# PTC_Control_V2.net
KiCad netlist of a schematic drawn in EAGLE
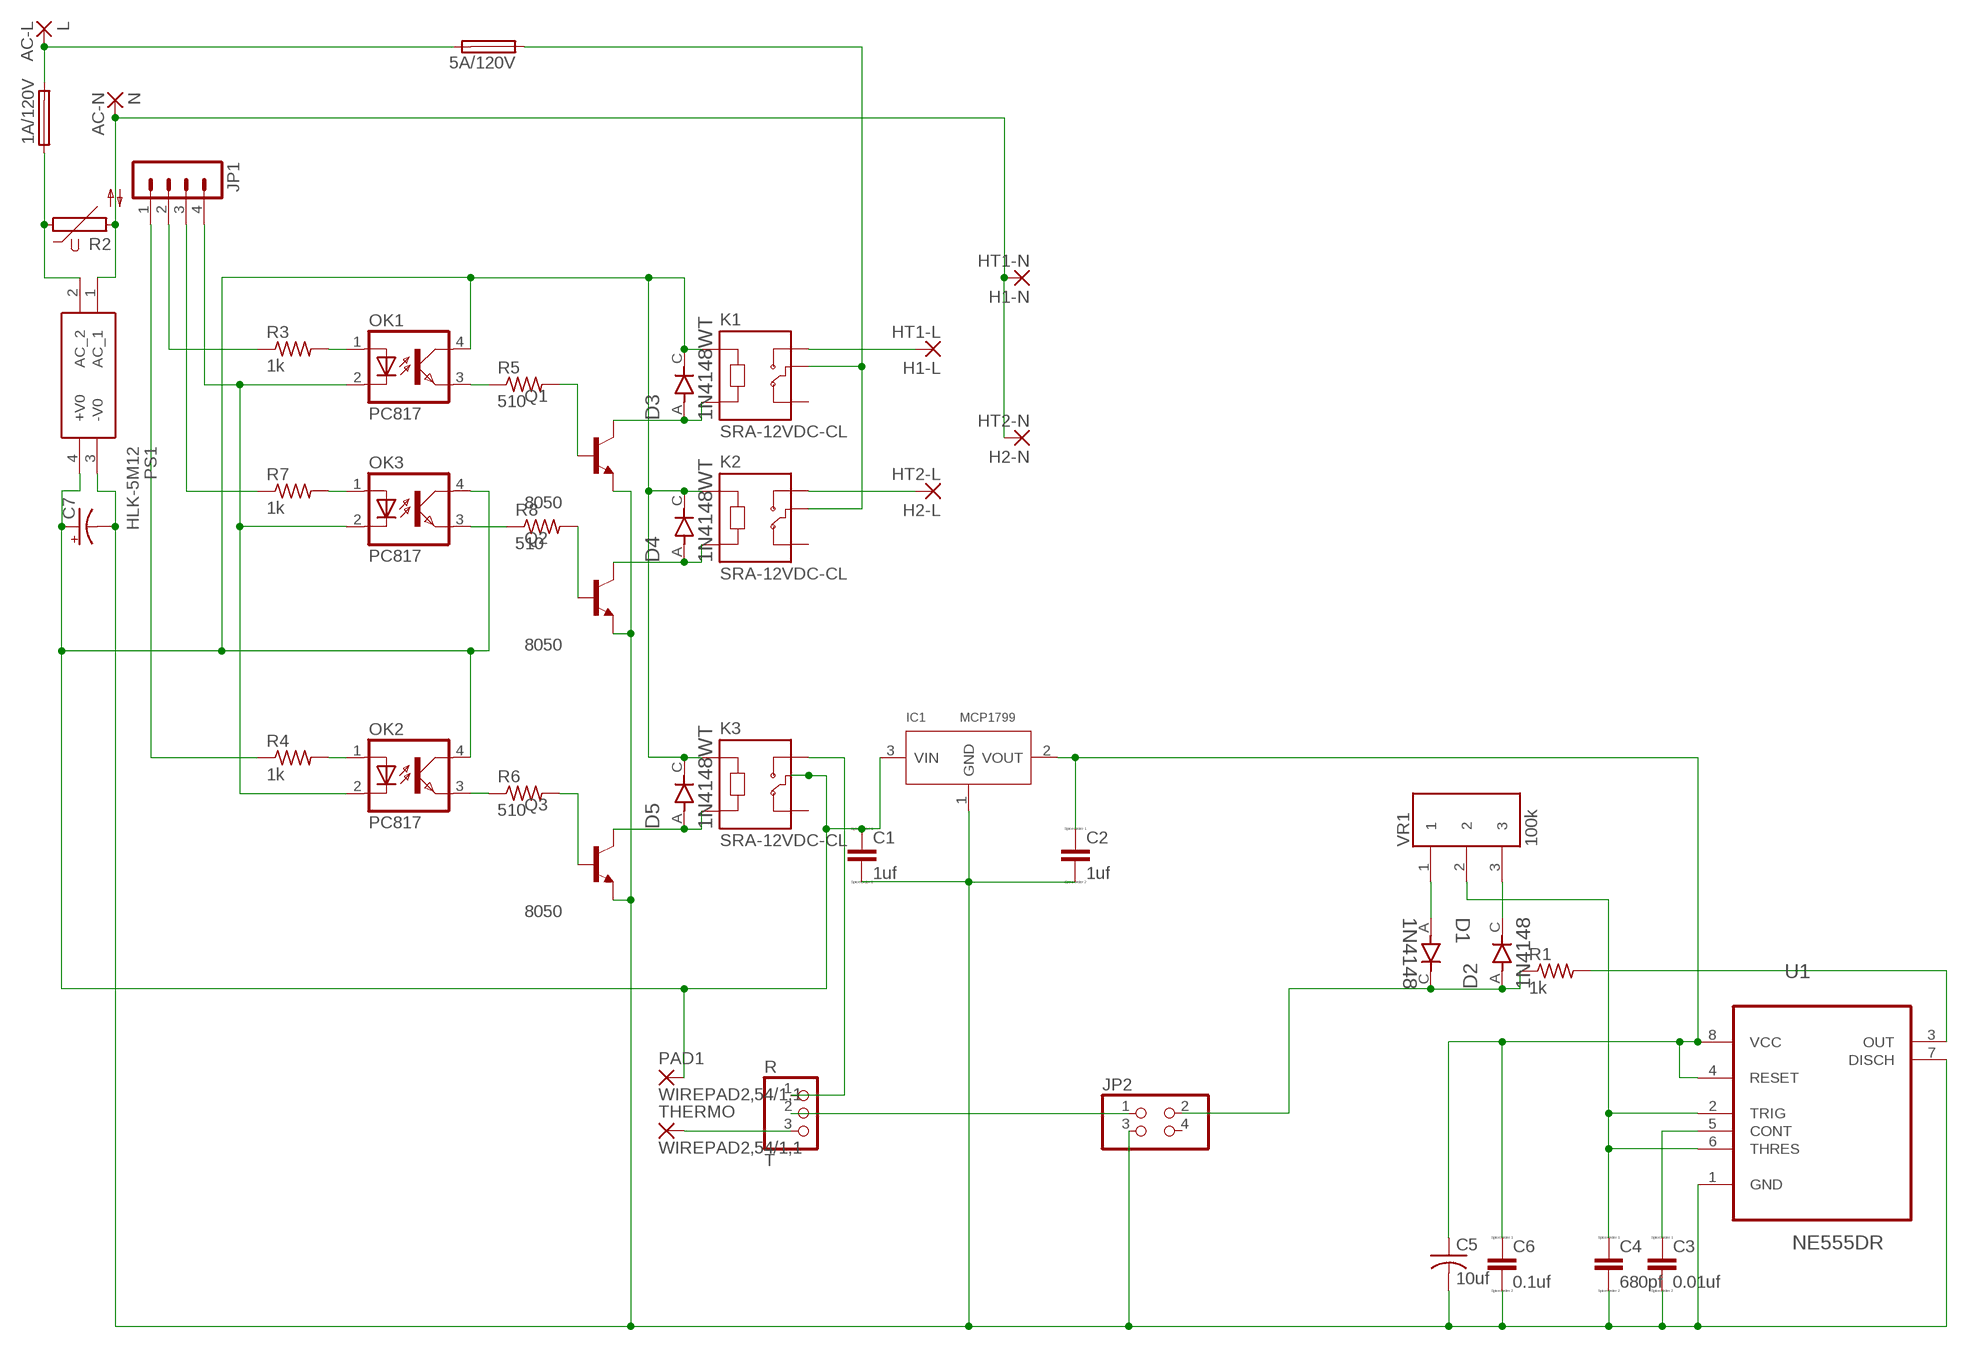
[diagram p0: schematic, sheet 1]

(export (version "E")
  (design (tool "Eeschema 10.0.6"))
  (components
    (comp (ref "1A/120V")
      (value "SH25")
      (footprint "eagle-import:SH25")
      (fields (field (name "MF") "SCHURTER") (field (name "MPN") "0031.8211"))
      (libsource (lib "eagle-import") (part "SH25"))
    )
    (comp (ref "5A/120V")
      (value "SH25")
      (footprint "eagle-import:SH25")
      (fields (field (name "MF") "SCHURTER") (field (name "MPN") "0031.8211"))
      (libsource (lib "eagle-import") (part "SH25"))
    )
    (comp (ref "C1")
      (value "1uf")
      (footprint "eagle-import:C0805")
      (libsource (lib "eagle-import") (part "C"))
    )
    (comp (ref "C2")
      (value "1uf")
      (footprint "eagle-import:C0805")
      (libsource (lib "eagle-import") (part "C"))
    )
    (comp (ref "C3")
      (value "0.01uf")
      (footprint "eagle-import:C0805")
      (libsource (lib "eagle-import") (part "C"))
    )
    (comp (ref "C4")
      (value "680pf")
      (footprint "eagle-import:C0805")
      (libsource (lib "eagle-import") (part "C"))
    )
    (comp (ref "C5")
      (value "10uf")
      (footprint "eagle-import:C1206")
      (libsource (lib "eagle-import") (part "C-USC1206"))
    )
    (comp (ref "C6")
      (value "0.1uf")
      (footprint "eagle-import:C0805")
      (libsource (lib "eagle-import") (part "C"))
    )
    (comp (ref "C7")
      (value "CPOL-USE3.5-8")
      (footprint "eagle-import:E3,5-8")
      (libsource (lib "eagle-import") (part "CPOL-USE3.5-8"))
    )
    (comp (ref "D1")
      (value "1N4148")
      (footprint "eagle-import:SODFL1608X70N")
      (fields (field (name "MF") "ON Semiconductor") (field (name "MP") "1N4148WT"))
      (libsource (lib "eagle-import") (part "1N4148WT"))
    )
    (comp (ref "D2")
      (value "1N4148")
      (footprint "eagle-import:SODFL1608X70N")
      (fields (field (name "MF") "ON Semiconductor") (field (name "MP") "1N4148WT"))
      (libsource (lib "eagle-import") (part "1N4148WT"))
    )
    (comp (ref "D3")
      (value "1N4148WT")
      (footprint "eagle-import:SODFL1608X70N")
      (fields (field (name "MF") "ON Semiconductor"))
      (libsource (lib "eagle-import") (part "1N4148WT"))
    )
    (comp (ref "D4")
      (value "1N4148WT")
      (footprint "eagle-import:SODFL1608X70N")
      (fields (field (name "MF") "ON Semiconductor"))
      (libsource (lib "eagle-import") (part "1N4148WT"))
    )
    (comp (ref "D5")
      (value "1N4148WT")
      (footprint "eagle-import:SODFL1608X70N")
      (fields (field (name "MF") "ON Semiconductor"))
      (libsource (lib "eagle-import") (part "1N4148WT"))
    )
    (comp (ref "H1-L")
      (value "HT1-L")
      (footprint "eagle-import:3,17_1,2")
      (libsource (lib "eagle-import") (part "WIREPAD3,17/1,2"))
    )
    (comp (ref "H1-N")
      (value "HT1-N")
      (footprint "eagle-import:3,17_1,2")
      (libsource (lib "eagle-import") (part "WIREPAD3,17/1,2"))
    )
    (comp (ref "H2-L")
      (value "HT2-L")
      (footprint "eagle-import:3,17_1,2")
      (libsource (lib "eagle-import") (part "WIREPAD3,17/1,2"))
    )
    (comp (ref "H2-N")
      (value "HT2-N")
      (footprint "eagle-import:3,17_1,2")
      (libsource (lib "eagle-import") (part "WIREPAD3,17/1,2"))
    )
    (comp (ref "IC1")
      (value "MCP1799")
      (footprint "eagle-import:SOT-23")
      (fields (field (name "MF") "Torex") (field (name "MP") "XC6206P252MR-G"))
      (libsource (lib "eagle-import") (part "PMIC-LDO-XC6206P252MR-G(SOT23)"))
    )
    (comp (ref "JP1")
      (value "MA04-1")
      (footprint "eagle-import:MA04-1")
      (libsource (lib "eagle-import") (part "MA04-1"))
    )
    (comp (ref "JP2")
      (value "PINHD-2X2")
      (footprint "eagle-import:2X02")
      (libsource (lib "eagle-import") (part "PINHD-2X2"))
    )
    (comp (ref "K1")
      (value "SRA-12VDC-CL")
      (footprint "eagle-import:RELAY_1-1721150-3")
      (fields
        (field (name "COMMENT") "1-1721150-3")
        (field (name "MF") "TE Connectivity")
        (field (name "MP") "ORWH-SH-112D1F,000")
      )
      (libsource (lib "eagle-import") (part "1-1721150-3"))
    )
    (comp (ref "K2")
      (value "SRA-12VDC-CL")
      (footprint "eagle-import:RELAY_1-1721150-3")
      (fields
        (field (name "COMMENT") "1-1721150-3")
        (field (name "MF") "TE Connectivity")
        (field (name "MP") "ORWH-SH-112D1F,000")
      )
      (libsource (lib "eagle-import") (part "1-1721150-3"))
    )
    (comp (ref "K3")
      (value "SRA-12VDC-CL")
      (footprint "eagle-import:RELAY_1-1721150-3")
      (fields
        (field (name "COMMENT") "1-1721150-3")
        (field (name "MF") "TE Connectivity")
        (field (name "MP") "ORWH-SH-112D1F,000")
      )
      (libsource (lib "eagle-import") (part "1-1721150-3"))
    )
    (comp (ref "L")
      (value "AC-L")
      (footprint "eagle-import:3,81_1,4")
      (libsource (lib "eagle-import") (part "WIREPAD3,81/1,4"))
    )
    (comp (ref "N")
      (value "AC-N")
      (footprint "eagle-import:3,81_1,4")
      (libsource (lib "eagle-import") (part "WIREPAD3,81/1,4"))
    )
    (comp (ref "OK1")
      (value "PC817")
      (footprint "eagle-import:DIL04")
      (fields (field (name "MPN") "PC817X4J000F"))
      (libsource (lib "eagle-import") (part "PC817"))
    )
    (comp (ref "OK2")
      (value "PC817")
      (footprint "eagle-import:DIL04")
      (fields (field (name "MPN") "PC817X4J000F"))
      (libsource (lib "eagle-import") (part "PC817"))
    )
    (comp (ref "OK3")
      (value "PC817")
      (footprint "eagle-import:DIL04")
      (fields (field (name "MPN") "PC817X4J000F"))
      (libsource (lib "eagle-import") (part "PC817"))
    )
    (comp (ref "PAD1")
      (value "WIREPAD2,54/1,1")
      (footprint "eagle-import:2,54_1,1")
      (libsource (lib "eagle-import") (part "WIREPAD2,54/1,1"))
    )
    (comp (ref "PS1")
      (value "HLK-5M12")
      (footprint "eagle-import:HLK5M12")
      (libsource (lib "eagle-import") (part "HLK-5M12"))
    )
    (comp (ref "Q1")
      (value "8050")
      (footprint "eagle-import:TRANS_MMSS8050-H-TP")
      (fields (field (name "MF") "Micro Commercial") (field (name "MP") "MMSS8050-H-TP"))
      (libsource (lib "eagle-import") (part "MMSS8050-H-TP"))
    )
    (comp (ref "Q2")
      (value "8050")
      (footprint "eagle-import:TRANS_MMSS8050-H-TP")
      (fields (field (name "MF") "Micro Commercial") (field (name "MP") "MMSS8050-H-TP"))
      (libsource (lib "eagle-import") (part "MMSS8050-H-TP"))
    )
    (comp (ref "Q3")
      (value "8050")
      (footprint "eagle-import:TRANS_MMSS8050-H-TP")
      (fields (field (name "MF") "Micro Commercial") (field (name "MP") "MMSS8050-H-TP"))
      (libsource (lib "eagle-import") (part "MMSS8050-H-TP"))
    )
    (comp (ref "R")
      (value "T")
      (footprint "eagle-import:1X03")
      (libsource (lib "eagle-import") (part "PINHD-1X3"))
    )
    (comp (ref "R1")
      (value "1k")
      (footprint "eagle-import:R0805")
      (libsource (lib "eagle-import") (part "R-US_R0805"))
    )
    (comp (ref "R2")
      (value "S10K250")
      (footprint "eagle-import:S10K250")
      (libsource (lib "eagle-import") (part "S10K250"))
    )
    (comp (ref "R3")
      (value "1k")
      (footprint "eagle-import:R0805")
      (libsource (lib "eagle-import") (part "R-US_R0805"))
    )
    (comp (ref "R4")
      (value "1k")
      (footprint "eagle-import:R0805")
      (libsource (lib "eagle-import") (part "R-US_R0805"))
    )
    (comp (ref "R5")
      (value "510")
      (footprint "eagle-import:R0805")
      (libsource (lib "eagle-import") (part "R-US_R0805"))
    )
    (comp (ref "R6")
      (value "510")
      (footprint "eagle-import:R0805")
      (libsource (lib "eagle-import") (part "R-US_R0805"))
    )
    (comp (ref "R7")
      (value "1k")
      (footprint "eagle-import:R0805")
      (libsource (lib "eagle-import") (part "R-US_R0805"))
    )
    (comp (ref "R8")
      (value "510")
      (footprint "eagle-import:R0805")
      (libsource (lib "eagle-import") (part "R-US_R0805"))
    )
    (comp (ref "THERMO")
      (value "WIREPAD2,54/1,1")
      (footprint "eagle-import:2,54_1,1")
      (libsource (lib "eagle-import") (part "WIREPAD2,54/1,1"))
    )
    (comp (ref "U1")
      (value "NE555DR")
      (footprint "eagle-import:SOIC127P600X175-8N")
      (libsource (lib "eagle-import") (part "NE555DR"))
    )
    (comp (ref "VR1")
      (value "100k")
      (footprint "eagle-import:TRIM_416XA503P")
      (fields
        (field (name "COMMENT") "1623895-9")
        (field (name "MF") "TE Connectivity")
        (field (name "MP") "416XA503P")
      )
      (libsource (lib "eagle-import") (part "416XA503P"))
    )
  )
  (nets
    (net (code "1") (name "Net-(5A/120V-Pad1)") (class "Default")
      (node (ref "5A/120V") (pin "1") (pinfunction "1_1") (pintype "passive"))
      (node (ref "K1") (pin "COM") (pinfunction "COM_COM") (pintype "passive"))
      (node (ref "K2") (pin "COM") (pinfunction "COM_COM") (pintype "passive"))
    )
    (net (code "2") (name "Net-(D1-PadA)") (class "Default")
      (node (ref "D1") (pin "A") (pinfunction "A_A") (pintype "passive"))
      (node (ref "VR1") (pin "1") (pinfunction "1_1") (pintype "passive"))
    )
    (net (code "3") (name "Net-(D1-PadC)") (class "Default")
      (node (ref "D1") (pin "C") (pinfunction "C_C") (pintype "passive"))
      (node (ref "D2") (pin "A") (pinfunction "A_A") (pintype "passive"))
      (node (ref "JP2") (pin "2") (pinfunction "2_2") (pintype "passive"))
      (node (ref "R1") (pin "1") (pinfunction "1_1") (pintype "passive"))
    )
    (net (code "4") (name "Net-(D2-PadC)") (class "Default")
      (node (ref "D2") (pin "C") (pinfunction "C_C") (pintype "passive"))
      (node (ref "VR1") (pin "3") (pinfunction "3_3") (pintype "passive"))
    )
    (net (code "5") (name "Net-(H1-L-P)") (class "Default")
      (node (ref "H1-L") (pin "1") (pinfunction "P_1") (pintype "passive"))
      (node (ref "K1") (pin "NO") (pinfunction "NO_NO") (pintype "passive"))
    )
    (net (code "6") (name "Net-(H1-N-P)") (class "Default")
      (node (ref "H1-N") (pin "1") (pinfunction "P_1") (pintype "passive"))
      (node (ref "H2-N") (pin "1") (pinfunction "P_1") (pintype "passive"))
      (node (ref "N") (pin "1") (pinfunction "P_1") (pintype "passive"))
      (node (ref "PS1") (pin "1") (pinfunction "AC_1_1") (pintype "bidirectional"))
      (node (ref "R2") (pin "2") (pinfunction "2_2") (pintype "passive"))
    )
    (net (code "7") (name "Net-(H2-L-P)") (class "Default")
      (node (ref "H2-L") (pin "1") (pinfunction "P_1") (pintype "passive"))
      (node (ref "K2") (pin "NO") (pinfunction "NO_NO") (pintype "passive"))
    )
    (net (code "8") (name "Net-(IC1-GND)") (class "Default")
      (node (ref "C1") (pin "2") (pinfunction "2_2") (pintype "passive"))
      (node (ref "C2") (pin "2") (pinfunction "2_2") (pintype "passive"))
      (node (ref "C3") (pin "2") (pinfunction "2_2") (pintype "passive"))
      (node (ref "C4") (pin "2") (pinfunction "2_2") (pintype "passive"))
      (node (ref "C5") (pin "2") (pinfunction "2_2") (pintype "passive"))
      (node (ref "C6") (pin "2") (pinfunction "2_2") (pintype "passive"))
      (node (ref "C7") (pin "-") (pinfunction "-_-") (pintype "passive"))
      (node (ref "IC1") (pin "1") (pinfunction "GND_1") (pintype "power_in"))
      (node (ref "JP2") (pin "3") (pinfunction "3_3") (pintype "passive"))
      (node (ref "PS1") (pin "3") (pinfunction "-V0_3") (pintype "bidirectional"))
      (node (ref "Q1") (pin "2") (pinfunction "E_2") (pintype "passive"))
      (node (ref "Q2") (pin "2") (pinfunction "E_2") (pintype "passive"))
      (node (ref "Q3") (pin "2") (pinfunction "E_2") (pintype "passive"))
      (node (ref "U1") (pin "1") (pinfunction "GND_1") (pintype "passive"))
      (node (ref "U1") (pin "7") (pinfunction "DISCH_7") (pintype "output"))
    )
    (net (code "9") (name "Net-(IC1-VIN)") (class "Default")
      (node (ref "C1") (pin "1") (pinfunction "1_1") (pintype "passive"))
      (node (ref "C7") (pin "+") (pinfunction "+_+") (pintype "passive"))
      (node (ref "D3") (pin "C") (pinfunction "C_C") (pintype "passive"))
      (node (ref "D4") (pin "C") (pinfunction "C_C") (pintype "passive"))
      (node (ref "D5") (pin "C") (pinfunction "C_C") (pintype "passive"))
      (node (ref "IC1") (pin "3") (pinfunction "VIN_3") (pintype "input"))
      (node (ref "K1") (pin "A1") (pinfunction "A1_A1") (pintype "passive"))
      (node (ref "K2") (pin "A1") (pinfunction "A1_A1") (pintype "passive"))
      (node (ref "K3") (pin "A1") (pinfunction "A1_A1") (pintype "passive"))
      (node (ref "K3") (pin "COM") (pinfunction "COM_COM") (pintype "passive"))
      (node (ref "OK1") (pin "4") (pinfunction "COL_4") (pintype "passive"))
      (node (ref "OK2") (pin "4") (pinfunction "COL_4") (pintype "passive"))
      (node (ref "OK3") (pin "4") (pinfunction "COL_4") (pintype "passive"))
      (node (ref "PAD1") (pin "1") (pinfunction "P_1") (pintype "passive"))
      (node (ref "PS1") (pin "4") (pinfunction "+V0_4") (pintype "bidirectional"))
    )
    (net (code "10") (name "Net-(IC1-VOUT)") (class "Default")
      (node (ref "C2") (pin "1") (pinfunction "1_1") (pintype "passive"))
      (node (ref "C5") (pin "1") (pinfunction "1_1") (pintype "passive"))
      (node (ref "C6") (pin "1") (pinfunction "1_1") (pintype "passive"))
      (node (ref "IC1") (pin "2") (pinfunction "VOUT_2") (pintype "output"))
      (node (ref "U1") (pin "4") (pinfunction "RESET_4") (pintype "input"))
      (node (ref "U1") (pin "8") (pinfunction "VCC_8") (pintype "power_in"))
    )
    (net (code "11") (name "Net-(JP1-Pad1)") (class "Default")
      (node (ref "JP1") (pin "1") (pinfunction "1_1") (pintype "passive"))
      (node (ref "R4") (pin "1") (pinfunction "1_1") (pintype "passive"))
    )
    (net (code "12") (name "Net-(JP1-Pad2)") (class "Default")
      (node (ref "JP1") (pin "2") (pinfunction "2_2") (pintype "passive"))
      (node (ref "R3") (pin "1") (pinfunction "1_1") (pintype "passive"))
    )
    (net (code "13") (name "Net-(JP1-Pad3)") (class "Default")
      (node (ref "JP1") (pin "3") (pinfunction "3_3") (pintype "passive"))
      (node (ref "R7") (pin "1") (pinfunction "1_1") (pintype "passive"))
    )
    (net (code "14") (name "Net-(JP2-Pad1)") (class "Default")
      (node (ref "JP2") (pin "1") (pinfunction "1_1") (pintype "passive"))
      (node (ref "R") (pin "2") (pinfunction "2_2") (pintype "passive"))
    )
    (net (code "15") (name "Net-(K3-PadNO)") (class "Default")
      (node (ref "K3") (pin "NO") (pinfunction "NO_NO") (pintype "passive"))
      (node (ref "R") (pin "1") (pinfunction "1_1") (pintype "passive"))
    )
    (net (code "16") (name "Net-(L-P)") (class "Default")
      (node (ref "1A/120V") (pin "2") (pinfunction "2_2") (pintype "passive"))
      (node (ref "5A/120V") (pin "2") (pinfunction "2_2") (pintype "passive"))
      (node (ref "L") (pin "1") (pinfunction "P_1") (pintype "passive"))
    )
    (net (code "17") (name "Net-(OK1-A)") (class "Default")
      (node (ref "OK1") (pin "1") (pinfunction "A_1") (pintype "passive"))
      (node (ref "R3") (pin "2") (pinfunction "2_2") (pintype "passive"))
    )
    (net (code "18") (name "Net-(OK1-C)") (class "Default")
      (node (ref "JP1") (pin "4") (pinfunction "4_4") (pintype "passive"))
      (node (ref "OK1") (pin "2") (pinfunction "C_2") (pintype "passive"))
      (node (ref "OK2") (pin "2") (pinfunction "C_2") (pintype "passive"))
      (node (ref "OK3") (pin "2") (pinfunction "C_2") (pintype "passive"))
    )
    (net (code "19") (name "Net-(OK1-EMIT)") (class "Default")
      (node (ref "OK1") (pin "3") (pinfunction "EMIT_3") (pintype "passive"))
      (node (ref "R5") (pin "1") (pinfunction "1_1") (pintype "passive"))
    )
    (net (code "20") (name "Net-(OK2-A)") (class "Default")
      (node (ref "OK2") (pin "1") (pinfunction "A_1") (pintype "passive"))
      (node (ref "R4") (pin "2") (pinfunction "2_2") (pintype "passive"))
    )
    (net (code "21") (name "Net-(OK2-EMIT)") (class "Default")
      (node (ref "OK2") (pin "3") (pinfunction "EMIT_3") (pintype "passive"))
      (node (ref "R6") (pin "1") (pinfunction "1_1") (pintype "passive"))
    )
    (net (code "22") (name "Net-(OK3-A)") (class "Default")
      (node (ref "OK3") (pin "1") (pinfunction "A_1") (pintype "passive"))
      (node (ref "R7") (pin "2") (pinfunction "2_2") (pintype "passive"))
    )
    (net (code "23") (name "Net-(OK3-EMIT)") (class "Default")
      (node (ref "OK3") (pin "3") (pinfunction "EMIT_3") (pintype "passive"))
      (node (ref "R8") (pin "1") (pinfunction "1_1") (pintype "passive"))
    )
    (net (code "24") (name "Net-(PS1-AC_2)") (class "Default")
      (node (ref "1A/120V") (pin "1") (pinfunction "1_1") (pintype "passive"))
      (node (ref "PS1") (pin "2") (pinfunction "AC_2_2") (pintype "bidirectional"))
      (node (ref "R2") (pin "1") (pinfunction "1_1") (pintype "passive"))
    )
    (net (code "25") (name "Net-(Q1-B)") (class "Default")
      (node (ref "Q1") (pin "1") (pinfunction "B_1") (pintype "passive"))
      (node (ref "R5") (pin "2") (pinfunction "2_2") (pintype "passive"))
    )
    (net (code "26") (name "Net-(Q1-C)") (class "Default")
      (node (ref "D3") (pin "A") (pinfunction "A_A") (pintype "passive"))
      (node (ref "K1") (pin "A2") (pinfunction "A2_A2") (pintype "passive"))
      (node (ref "Q1") (pin "3") (pinfunction "C_3") (pintype "passive"))
    )
    (net (code "27") (name "Net-(Q2-B)") (class "Default")
      (node (ref "Q2") (pin "1") (pinfunction "B_1") (pintype "passive"))
      (node (ref "R8") (pin "2") (pinfunction "2_2") (pintype "passive"))
    )
    (net (code "28") (name "Net-(Q2-C)") (class "Default")
      (node (ref "D4") (pin "A") (pinfunction "A_A") (pintype "passive"))
      (node (ref "K2") (pin "A2") (pinfunction "A2_A2") (pintype "passive"))
      (node (ref "Q2") (pin "3") (pinfunction "C_3") (pintype "passive"))
    )
    (net (code "29") (name "Net-(Q3-B)") (class "Default")
      (node (ref "Q3") (pin "1") (pinfunction "B_1") (pintype "passive"))
      (node (ref "R6") (pin "2") (pinfunction "2_2") (pintype "passive"))
    )
    (net (code "30") (name "Net-(Q3-C)") (class "Default")
      (node (ref "D5") (pin "A") (pinfunction "A_A") (pintype "passive"))
      (node (ref "K3") (pin "A2") (pinfunction "A2_A2") (pintype "passive"))
      (node (ref "Q3") (pin "3") (pinfunction "C_3") (pintype "passive"))
    )
    (net (code "31") (name "Net-(THERMO-P)") (class "Default")
      (node (ref "R") (pin "3") (pinfunction "3_3") (pintype "passive"))
      (node (ref "THERMO") (pin "1") (pinfunction "P_1") (pintype "passive"))
    )
    (net (code "32") (name "Net-(U1-CONT)") (class "Default")
      (node (ref "C3") (pin "1") (pinfunction "1_1") (pintype "passive"))
      (node (ref "U1") (pin "5") (pinfunction "CONT_5") (pintype "input"))
    )
    (net (code "33") (name "Net-(U1-OUT)") (class "Default")
      (node (ref "R1") (pin "2") (pinfunction "2_2") (pintype "passive"))
      (node (ref "U1") (pin "3") (pinfunction "OUT_3") (pintype "output"))
    )
    (net (code "34") (name "Net-(U1-THRES)") (class "Default")
      (node (ref "C4") (pin "1") (pinfunction "1_1") (pintype "passive"))
      (node (ref "U1") (pin "2") (pinfunction "TRIG_2") (pintype "input"))
      (node (ref "U1") (pin "6") (pinfunction "THRES_6") (pintype "input"))
      (node (ref "VR1") (pin "2") (pinfunction "2_2") (pintype "passive"))
    )
    (net (code "35") (name "unconnected-(JP2-Pad4)") (class "Default")
      (node (ref "JP2") (pin "4") (pinfunction "4_4") (pintype "passive"))
    )
    (net (code "36") (name "unconnected-(K1-PadNC)") (class "Default")
      (node (ref "K1") (pin "NC") (pinfunction "NC_NC") (pintype "passive"))
    )
    (net (code "37") (name "unconnected-(K2-PadNC)") (class "Default")
      (node (ref "K2") (pin "NC") (pinfunction "NC_NC") (pintype "passive"))
    )
    (net (code "38") (name "unconnected-(K3-PadNC)") (class "Default")
      (node (ref "K3") (pin "NC") (pinfunction "NC_NC") (pintype "passive"))
    )
  )
)
